# 5V_DCDC_Conv.net
KiCad netlist of a schematic drawn in Altium Designer
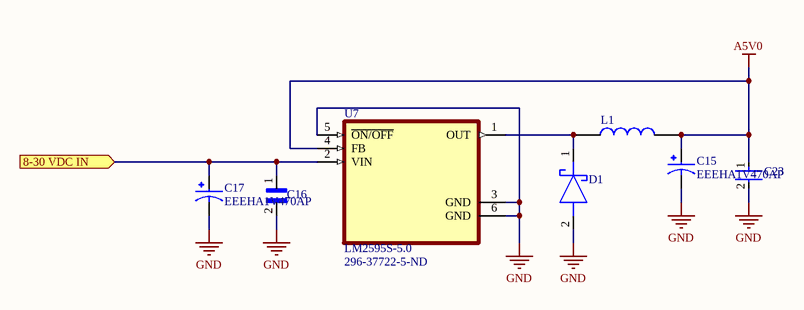
[diagram p0: 5V_DCDC_Conv.SchDoc]

(export (version "E")
  (design (tool "Eeschema 10.0.6"))
  (components
    (comp (ref "C15")
      (value "EEEHA1V470AP")
      (footprint "CAP_EEEHA1V470AP")
      (description "47ÂµF 35V Aluminum Electrolytic Capacitors Radial, Can - SMD 1000 Hrs @ 105Â°C")
      (fields (field (name "MF") "Panasonic") (field (name "MP") "EEE-HA1V470AP"))
      (libsource (lib "EEEHA1V470AP") (part "EEEHA1V470AP"))
    )
    (comp (ref "C16")
      (value "C0805C104M5UACTU")
      (footprint "CAPC2012X88N")
      (description "0.1ÂµF Â±20% 50V Ceramic Capacitor Z5U 0805 _2012 Metric_")
      (fields (field (name "MF") "KEMET"))
      (libsource (lib "0.1uF_Cap_C0805C104M5UACTU") (part "C0805C104M5UACTU"))
    )
    (comp (ref "C17")
      (value "EEEHA1V470AP")
      (footprint "CAP_EEEHA1V470AP")
      (description "47ÂµF 35V Aluminum Electrolytic Capacitors Radial, Can - SMD 1000 Hrs @ 105Â°C")
      (fields (field (name "MF") "Panasonic") (field (name "MP") "EEE-HA1V470AP"))
      (libsource (lib "EEEHA1V470AP") (part "EEEHA1V470AP"))
    )
    (comp (ref "C23")
      (value "C0603C104K5RACTU")
      (footprint "FP-C0603C-CF-IPC_A")
      (description "Multilayer Ceramic Capacitors (MLCC) - SMD/SMT 50volts 0.1uF X7R 10%")
      (fields (field (name "MANUFACTURER") "KEMET") (field (name "TOLERANCE") "10%"))
      (libsource (lib "Replacements") (part "C0603C104K5RACTU"))
    )
    (comp (ref "D1")
      (value "SS34-E3_57T")
      (footprint "DIOM7959X262N")
      (description "Schottky Diode")
      (fields
        (field (name "MANUFACTURER_PART_NUMBER") "SS34-E3/57T")
        (field (name "MOUSER PART NUMBER") "625-SS34-E3")
      )
      (libsource (lib "SamacSys") (part "SS34-E3_57T"))
    )
    (comp (ref "L1")
      (value "LQH3NPH101MMEL")
      (footprint "IND_LQH3NPH101MMEL")
      (description "FIXED IND 10UH 1280MA POWRTRNAUT")
      (libsource (lib "100uH_Ind_LQH3NPH101MMEL") (part "LQH3NPH101MMEL"))
    )
    (comp (ref "U7")
      (value "LM2595S-5.0")
      (footprint "VREG_TPS79625KTTR")
      (description "SIMPLE SWITCHERé›»æºè½‰æ›å™¨150 KHz 1Aé™å£“ç©©å£“å™¨5-DDPAK / TO-263")
      (fields
        (field (name "MF") "Texas Instruments")
        (field (name "SUPPLIER PART NUMBER 1") "296-37722-5-ND")
      )
      (libsource (lib "IC_LM2595S-5.0") (part "LM2595S-5.0"))
    )
  )
  (nets
    (net (code "1") (name "/8-30 VDC IN") (class "Default")
      (node (ref "C16") (pin "1") (pinfunction "1_1") (pintype "passive"))
      (node (ref "C17") (pin "1") (pinfunction "1_1") (pintype "passive"))
      (node (ref "U7") (pin "2") (pinfunction "VIN_2") (pintype "input"))
    )
    (net (code "2") (name "A5V0") (class "Default")
      (node (ref "C15") (pin "1") (pinfunction "1_1") (pintype "passive"))
      (node (ref "C23") (pin "1") (pinfunction "1_1") (pintype "passive"))
      (node (ref "L1") (pin "2") (pinfunction "2_2") (pintype "passive"))
      (node (ref "U7") (pin "4") (pinfunction "FB_4") (pintype "input"))
    )
    (net (code "3") (name "GND") (class "Default")
      (node (ref "C15") (pin "2") (pinfunction "2_2") (pintype "passive"))
      (node (ref "C16") (pin "2") (pinfunction "2_2") (pintype "passive"))
      (node (ref "C17") (pin "2") (pinfunction "2_2") (pintype "passive"))
      (node (ref "C23") (pin "2") (pinfunction "2_2") (pintype "passive"))
      (node (ref "D1") (pin "2") (pinfunction "A_2") (pintype "passive"))
      (node (ref "U7") (pin "3") (pinfunction "GND_3") (pintype "power_in"))
      (node (ref "U7") (pin "5") (pinfunction "~{ON/OFF}_5") (pintype "input"))
      (node (ref "U7") (pin "6") (pinfunction "GND_6") (pintype "power_in"))
    )
    (net (code "4") (name "Net-(D1-K)") (class "Default")
      (node (ref "D1") (pin "1") (pinfunction "K_1") (pintype "passive"))
      (node (ref "L1") (pin "1") (pinfunction "1_1") (pintype "passive"))
      (node (ref "U7") (pin "1") (pinfunction "OUT_1") (pintype "output"))
    )
  )
)
